# PCB-CARR-CMB-1and2.net
KiCad netlist of a schematic drawn in EAGLE
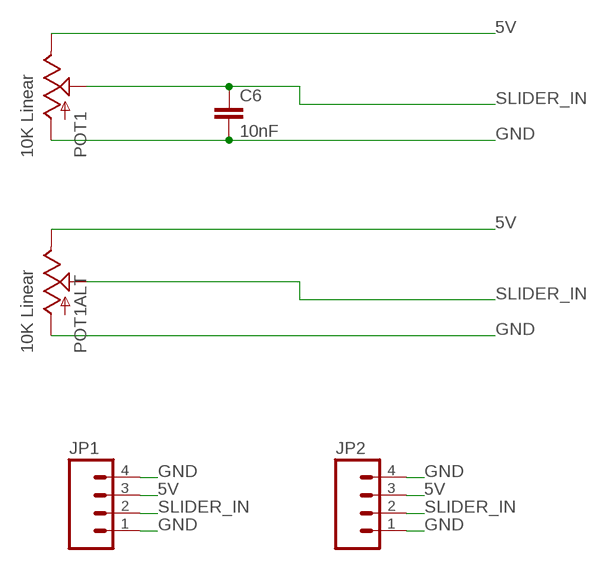
[diagram p0: schematic, sheet 1]

(export (version "E")
  (design (tool "Eeschema 10.0.6"))
  (components
    (comp (ref "C6")
      (value "10nF")
      (footprint "eagle-import:0603-CAP")
      (libsource (lib "eagle-import") (part "CAP0603-CAP"))
    )
    (comp (ref "JP1")
      (value "M04PTH")
      (footprint "eagle-import:1X04")
      (libsource (lib "eagle-import") (part "M04PTH"))
    )
    (comp (ref "JP2")
      (value "M04PTH")
      (footprint "eagle-import:1X04")
      (libsource (lib "eagle-import") (part "M04PTH"))
    )
    (comp (ref "POT1")
      (value "10K Linear")
      (footprint "eagle-import:SLIDER20")
      (libsource (lib "eagle-import") (part "SLIDER20"))
    )
    (comp (ref "POT1ALT")
      (value "10K Linear")
      (footprint "eagle-import:SLIDER20")
      (libsource (lib "eagle-import") (part "SLIDER20"))
    )
  )
  (nets
    (net (code "1") (name "5V") (class "Default")
      (node (ref "JP1") (pin "3") (pinfunction "3_3") (pintype "passive"))
      (node (ref "JP2") (pin "3") (pinfunction "3_3") (pintype "passive"))
      (node (ref "POT1") (pin "1") (pinfunction "E_1") (pintype "passive"))
      (node (ref "POT1ALT") (pin "1") (pinfunction "E_1") (pintype "passive"))
    )
    (net (code "2") (name "GND") (class "Default")
      (node (ref "C6") (pin "2") (pinfunction "2_2") (pintype "passive"))
      (node (ref "JP1") (pin "1") (pinfunction "1_1") (pintype "passive"))
      (node (ref "JP1") (pin "4") (pinfunction "4_4") (pintype "passive"))
      (node (ref "JP2") (pin "1") (pinfunction "1_1") (pintype "passive"))
      (node (ref "JP2") (pin "4") (pinfunction "4_4") (pintype "passive"))
      (node (ref "POT1") (pin "3") (pinfunction "A_3") (pintype "passive"))
      (node (ref "POT1ALT") (pin "3") (pinfunction "A_3") (pintype "passive"))
    )
    (net (code "3") (name "SLIDER_IN") (class "Default")
      (node (ref "C6") (pin "1") (pinfunction "1_1") (pintype "passive"))
      (node (ref "JP1") (pin "2") (pinfunction "2_2") (pintype "passive"))
      (node (ref "JP2") (pin "2") (pinfunction "2_2") (pintype "passive"))
      (node (ref "POT1") (pin "2A") (pinfunction "S_2A") (pintype "passive"))
      (node (ref "POT1ALT") (pin "2A") (pinfunction "S_2A") (pintype "passive"))
    )
  )
)
